# Adafruit_VCNL4040.net
KiCad netlist of a schematic drawn in EAGLE
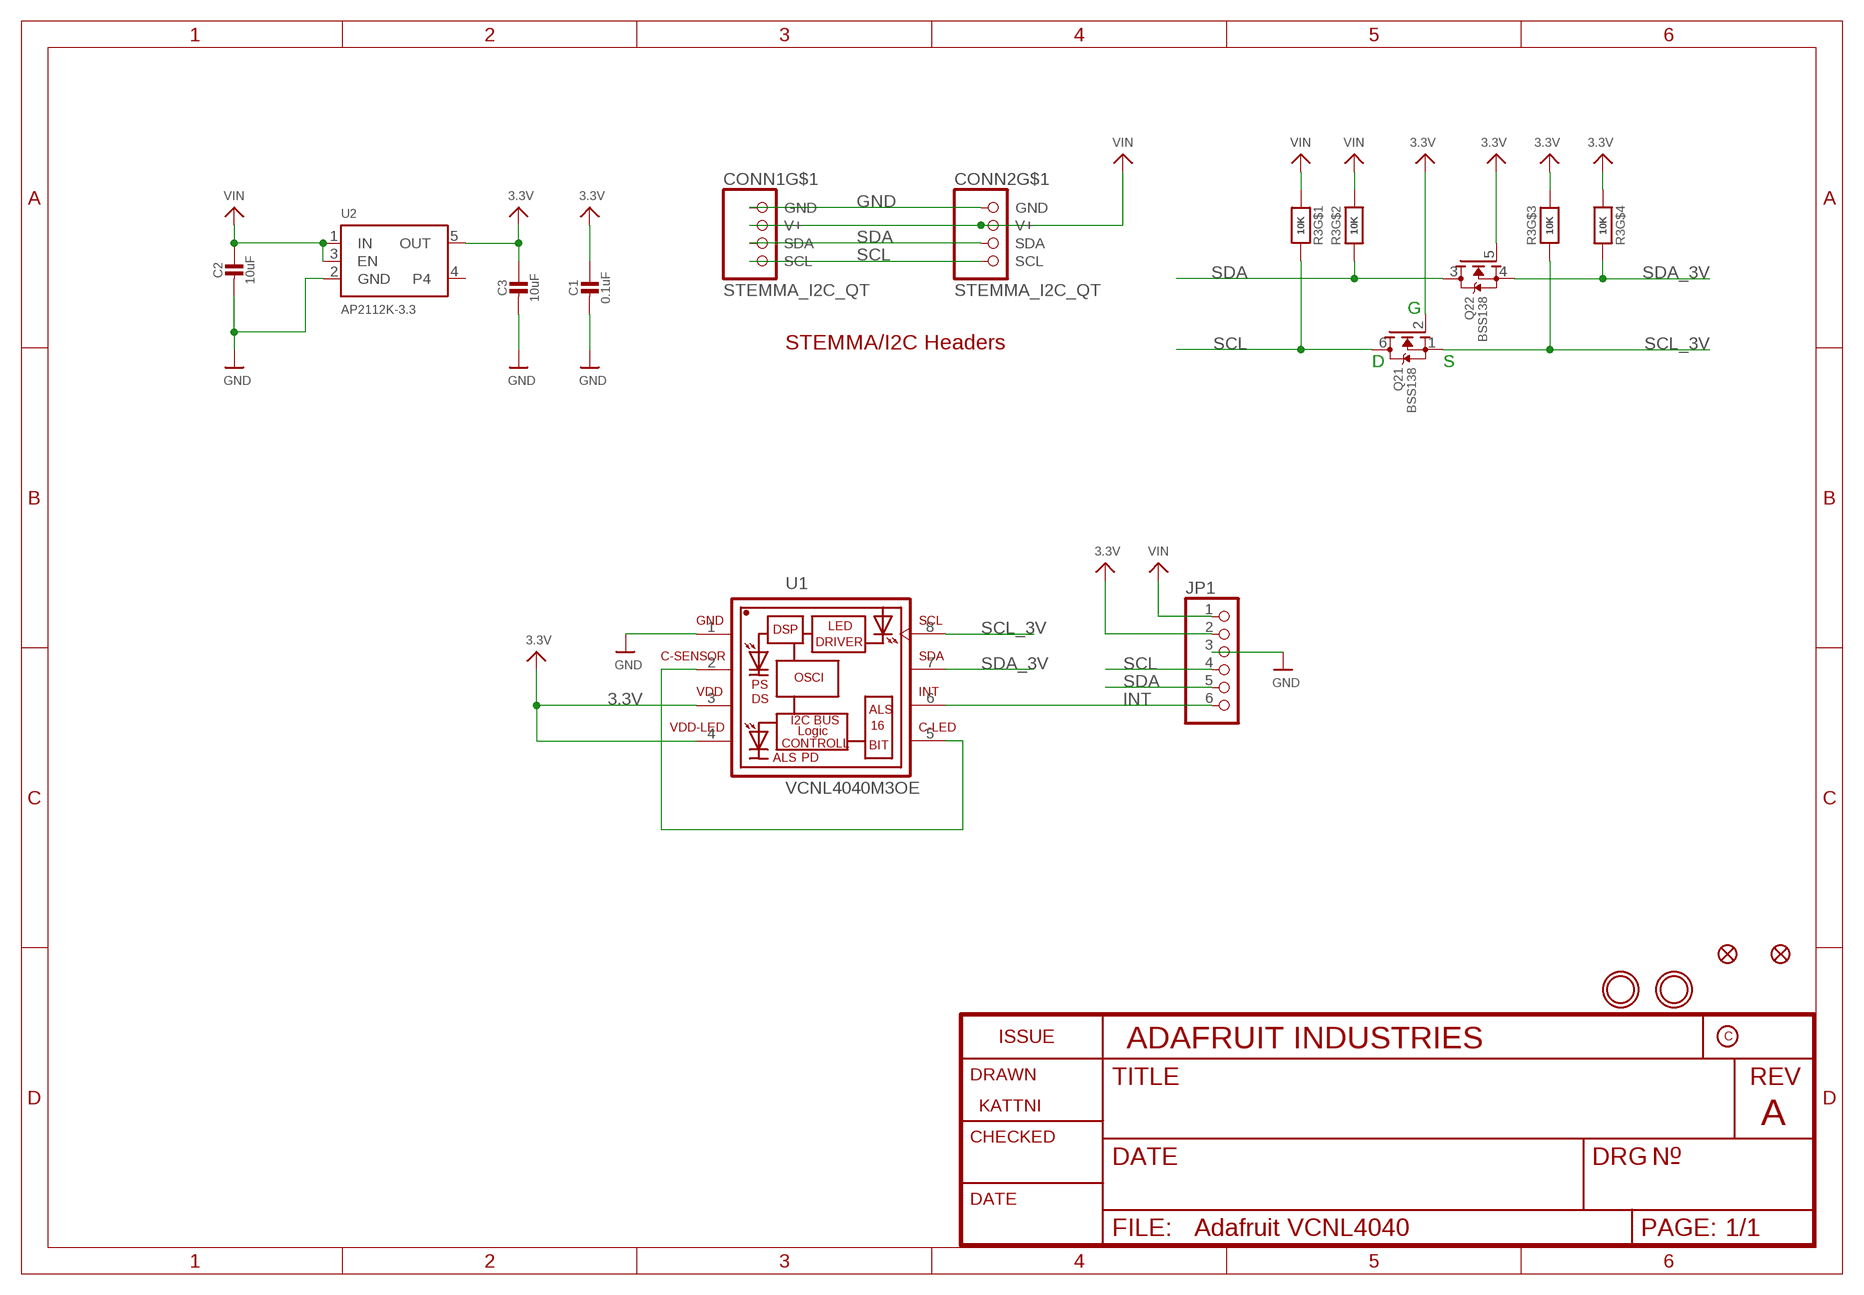
[diagram p0: schematic, sheet 1]

(export (version "E")
  (design (tool "Eeschema 10.0.6"))
  (components
    (comp (ref "C1")
      (value "0.1uF")
      (footprint "eagle-import:0603-NO")
      (libsource (lib "eagle-import") (part "CAP_CERAMIC0603_NO"))
    )
    (comp (ref "C2")
      (value "10uF")
      (footprint "eagle-import:0805-NO")
      (libsource (lib "eagle-import") (part "CAP_CERAMIC0805-NOOUTLINE"))
    )
    (comp (ref "C3")
      (value "10uF")
      (footprint "eagle-import:0805-NO")
      (libsource (lib "eagle-import") (part "CAP_CERAMIC0805-NOOUTLINE"))
    )
    (comp (ref "CONN1")
      (value "STEMMA_I2C_QT")
      (footprint "eagle-import:JST_SH4")
      (libsource (lib "eagle-import") (part "STEMMA_I2C_QT"))
    )
    (comp (ref "CONN2")
      (value "STEMMA_I2C_QT")
      (footprint "eagle-import:JST_SH4")
      (libsource (lib "eagle-import") (part "STEMMA_I2C_QT"))
    )
    (comp (ref "FID1")
      (value "FIDUCIAL_1MM")
      (footprint "eagle-import:FIDUCIAL_1MM")
      (libsource (lib "eagle-import") (part "FIDUCIAL_1MM"))
    )
    (comp (ref "FID2")
      (value "FIDUCIAL_1MM")
      (footprint "eagle-import:FIDUCIAL_1MM")
      (libsource (lib "eagle-import") (part "FIDUCIAL_1MM"))
    )
    (comp (ref "JP1")
      (value "HEADER-1X670MIL")
      (footprint "eagle-import:1X06_ROUND_70")
      (libsource (lib "eagle-import") (part "HEADER-1X670MIL"))
    )
    (comp (ref "Q2")
      (value "BSS138")
      (footprint "eagle-import:SOT363")
      (libsource (lib "eagle-import") (part "MOSFET-N_DUAL"))
    )
    (comp (ref "R3")
      (value "10K")
      (footprint "eagle-import:RESPACK_4X0603")
      (libsource (lib "eagle-import") (part "RESISTOR_4PACK"))
    )
    (comp (ref "U$3")
      (value "MOUNTINGHOLE2.5")
      (footprint "eagle-import:MOUNTINGHOLE_2.5_PLATED")
      (libsource (lib "eagle-import") (part "MOUNTINGHOLE2.5"))
    )
    (comp (ref "U$4")
      (value "MOUNTINGHOLE2.5")
      (footprint "eagle-import:MOUNTINGHOLE_2.5_PLATED")
      (libsource (lib "eagle-import") (part "MOUNTINGHOLE2.5"))
    )
    (comp (ref "U1")
      (value "VCNL4040M3OE")
      (footprint "eagle-import:VISHAY_VCNL4040_4X2X1.1")
      (fields (field (name "MF") "Vishay"))
      (libsource (lib "eagle-import") (part "VCNL4040M3OE"))
    )
    (comp (ref "U2")
      (value "AP2112K-3.3")
      (footprint "eagle-import:SOT23-5")
      (libsource (lib "eagle-import") (part "VREG_SOT23-5"))
    )
  )
  (nets
    (net (code "1") (name "/INT") (class "Default")
      (node (ref "JP1") (pin "6") (pinfunction "6_6") (pintype "passive"))
      (node (ref "U1") (pin "6") (pinfunction "INT_6") (pintype "output"))
    )
    (net (code "2") (name "/SCL") (class "Default")
      (node (ref "CONN1") (pin "4") (pinfunction "SCL_4") (pintype "passive"))
      (node (ref "CONN2") (pin "4") (pinfunction "SCL_4") (pintype "passive"))
      (node (ref "JP1") (pin "4") (pinfunction "4_4") (pintype "passive"))
      (node (ref "Q2") (pin "6") (pinfunction "D_6") (pintype "bidirectional"))
      (node (ref "R3") (pin "8") (pinfunction "2_8") (pintype "passive"))
    )
    (net (code "3") (name "/SCL_3V") (class "Default")
      (node (ref "Q2") (pin "1") (pinfunction "S_1") (pintype "bidirectional"))
      (node (ref "R3") (pin "3") (pinfunction "1_3") (pintype "passive"))
      (node (ref "U1") (pin "8") (pinfunction "SCL_8") (pintype "input"))
    )
    (net (code "4") (name "/SDA") (class "Default")
      (node (ref "CONN1") (pin "3") (pinfunction "SDA_3") (pintype "passive"))
      (node (ref "CONN2") (pin "3") (pinfunction "SDA_3") (pintype "passive"))
      (node (ref "JP1") (pin "5") (pinfunction "5_5") (pintype "passive"))
      (node (ref "Q2") (pin "3") (pinfunction "D_3") (pintype "bidirectional"))
      (node (ref "R3") (pin "7") (pinfunction "2_7") (pintype "passive"))
    )
    (net (code "5") (name "/SDA_3V") (class "Default")
      (node (ref "Q2") (pin "4") (pinfunction "S_4") (pintype "bidirectional"))
      (node (ref "R3") (pin "4") (pinfunction "1_4") (pintype "passive"))
      (node (ref "U1") (pin "7") (pinfunction "SDA_7") (pintype "bidirectional"))
    )
    (net (code "6") (name "3.3V") (class "Default")
      (node (ref "C1") (pin "1") (pinfunction "1_1") (pintype "passive"))
      (node (ref "C3") (pin "1") (pinfunction "1_1") (pintype "passive"))
      (node (ref "JP1") (pin "2") (pinfunction "2_2") (pintype "passive"))
      (node (ref "Q2") (pin "2") (pinfunction "G_2") (pintype "bidirectional"))
      (node (ref "Q2") (pin "5") (pinfunction "G_5") (pintype "bidirectional"))
      (node (ref "R3") (pin "5") (pinfunction "2_5") (pintype "passive"))
      (node (ref "R3") (pin "6") (pinfunction "2_6") (pintype "passive"))
      (node (ref "U1") (pin "3") (pinfunction "VDD_3") (pintype "power_in"))
      (node (ref "U1") (pin "4") (pinfunction "VDD-LED_4") (pintype "power_in"))
      (node (ref "U2") (pin "5") (pinfunction "OUT_5") (pintype "power_in"))
    )
    (net (code "7") (name "GND") (class "Default")
      (node (ref "C1") (pin "2") (pinfunction "2_2") (pintype "passive"))
      (node (ref "C2") (pin "2") (pinfunction "2_2") (pintype "passive"))
      (node (ref "C3") (pin "2") (pinfunction "2_2") (pintype "passive"))
      (node (ref "CONN1") (pin "1") (pinfunction "GND_1") (pintype "passive"))
      (node (ref "CONN2") (pin "1") (pinfunction "GND_1") (pintype "passive"))
      (node (ref "JP1") (pin "3") (pinfunction "3_3") (pintype "passive"))
      (node (ref "U1") (pin "1") (pinfunction "GND_1") (pintype "power_in"))
      (node (ref "U2") (pin "2") (pinfunction "GND_2") (pintype "power_in"))
    )
    (net (code "8") (name "Net-(U1-C-LED)") (class "Default")
      (node (ref "U1") (pin "2") (pinfunction "C-SENSOR_2") (pintype "output"))
      (node (ref "U1") (pin "5") (pinfunction "C-LED_5") (pintype "output"))
    )
    (net (code "9") (name "VIN") (class "Default")
      (node (ref "C2") (pin "1") (pinfunction "1_1") (pintype "passive"))
      (node (ref "CONN1") (pin "2") (pinfunction "V+_2") (pintype "passive"))
      (node (ref "CONN2") (pin "2") (pinfunction "V+_2") (pintype "passive"))
      (node (ref "JP1") (pin "1") (pinfunction "1_1") (pintype "passive"))
      (node (ref "R3") (pin "1") (pinfunction "1_1") (pintype "passive"))
      (node (ref "R3") (pin "2") (pinfunction "1_2") (pintype "passive"))
      (node (ref "U2") (pin "1") (pinfunction "IN_1") (pintype "power_in"))
      (node (ref "U2") (pin "3") (pinfunction "EN_3") (pintype "input"))
    )
    (net (code "10") (name "unconnected-(U2-P4-Pad4)") (class "Default")
      (node (ref "U2") (pin "4") (pinfunction "P4_4") (pintype "bidirectional"))
    )
  )
)
